# ERA_battery.net
KiCad netlist of a schematic drawn in EasyEDA
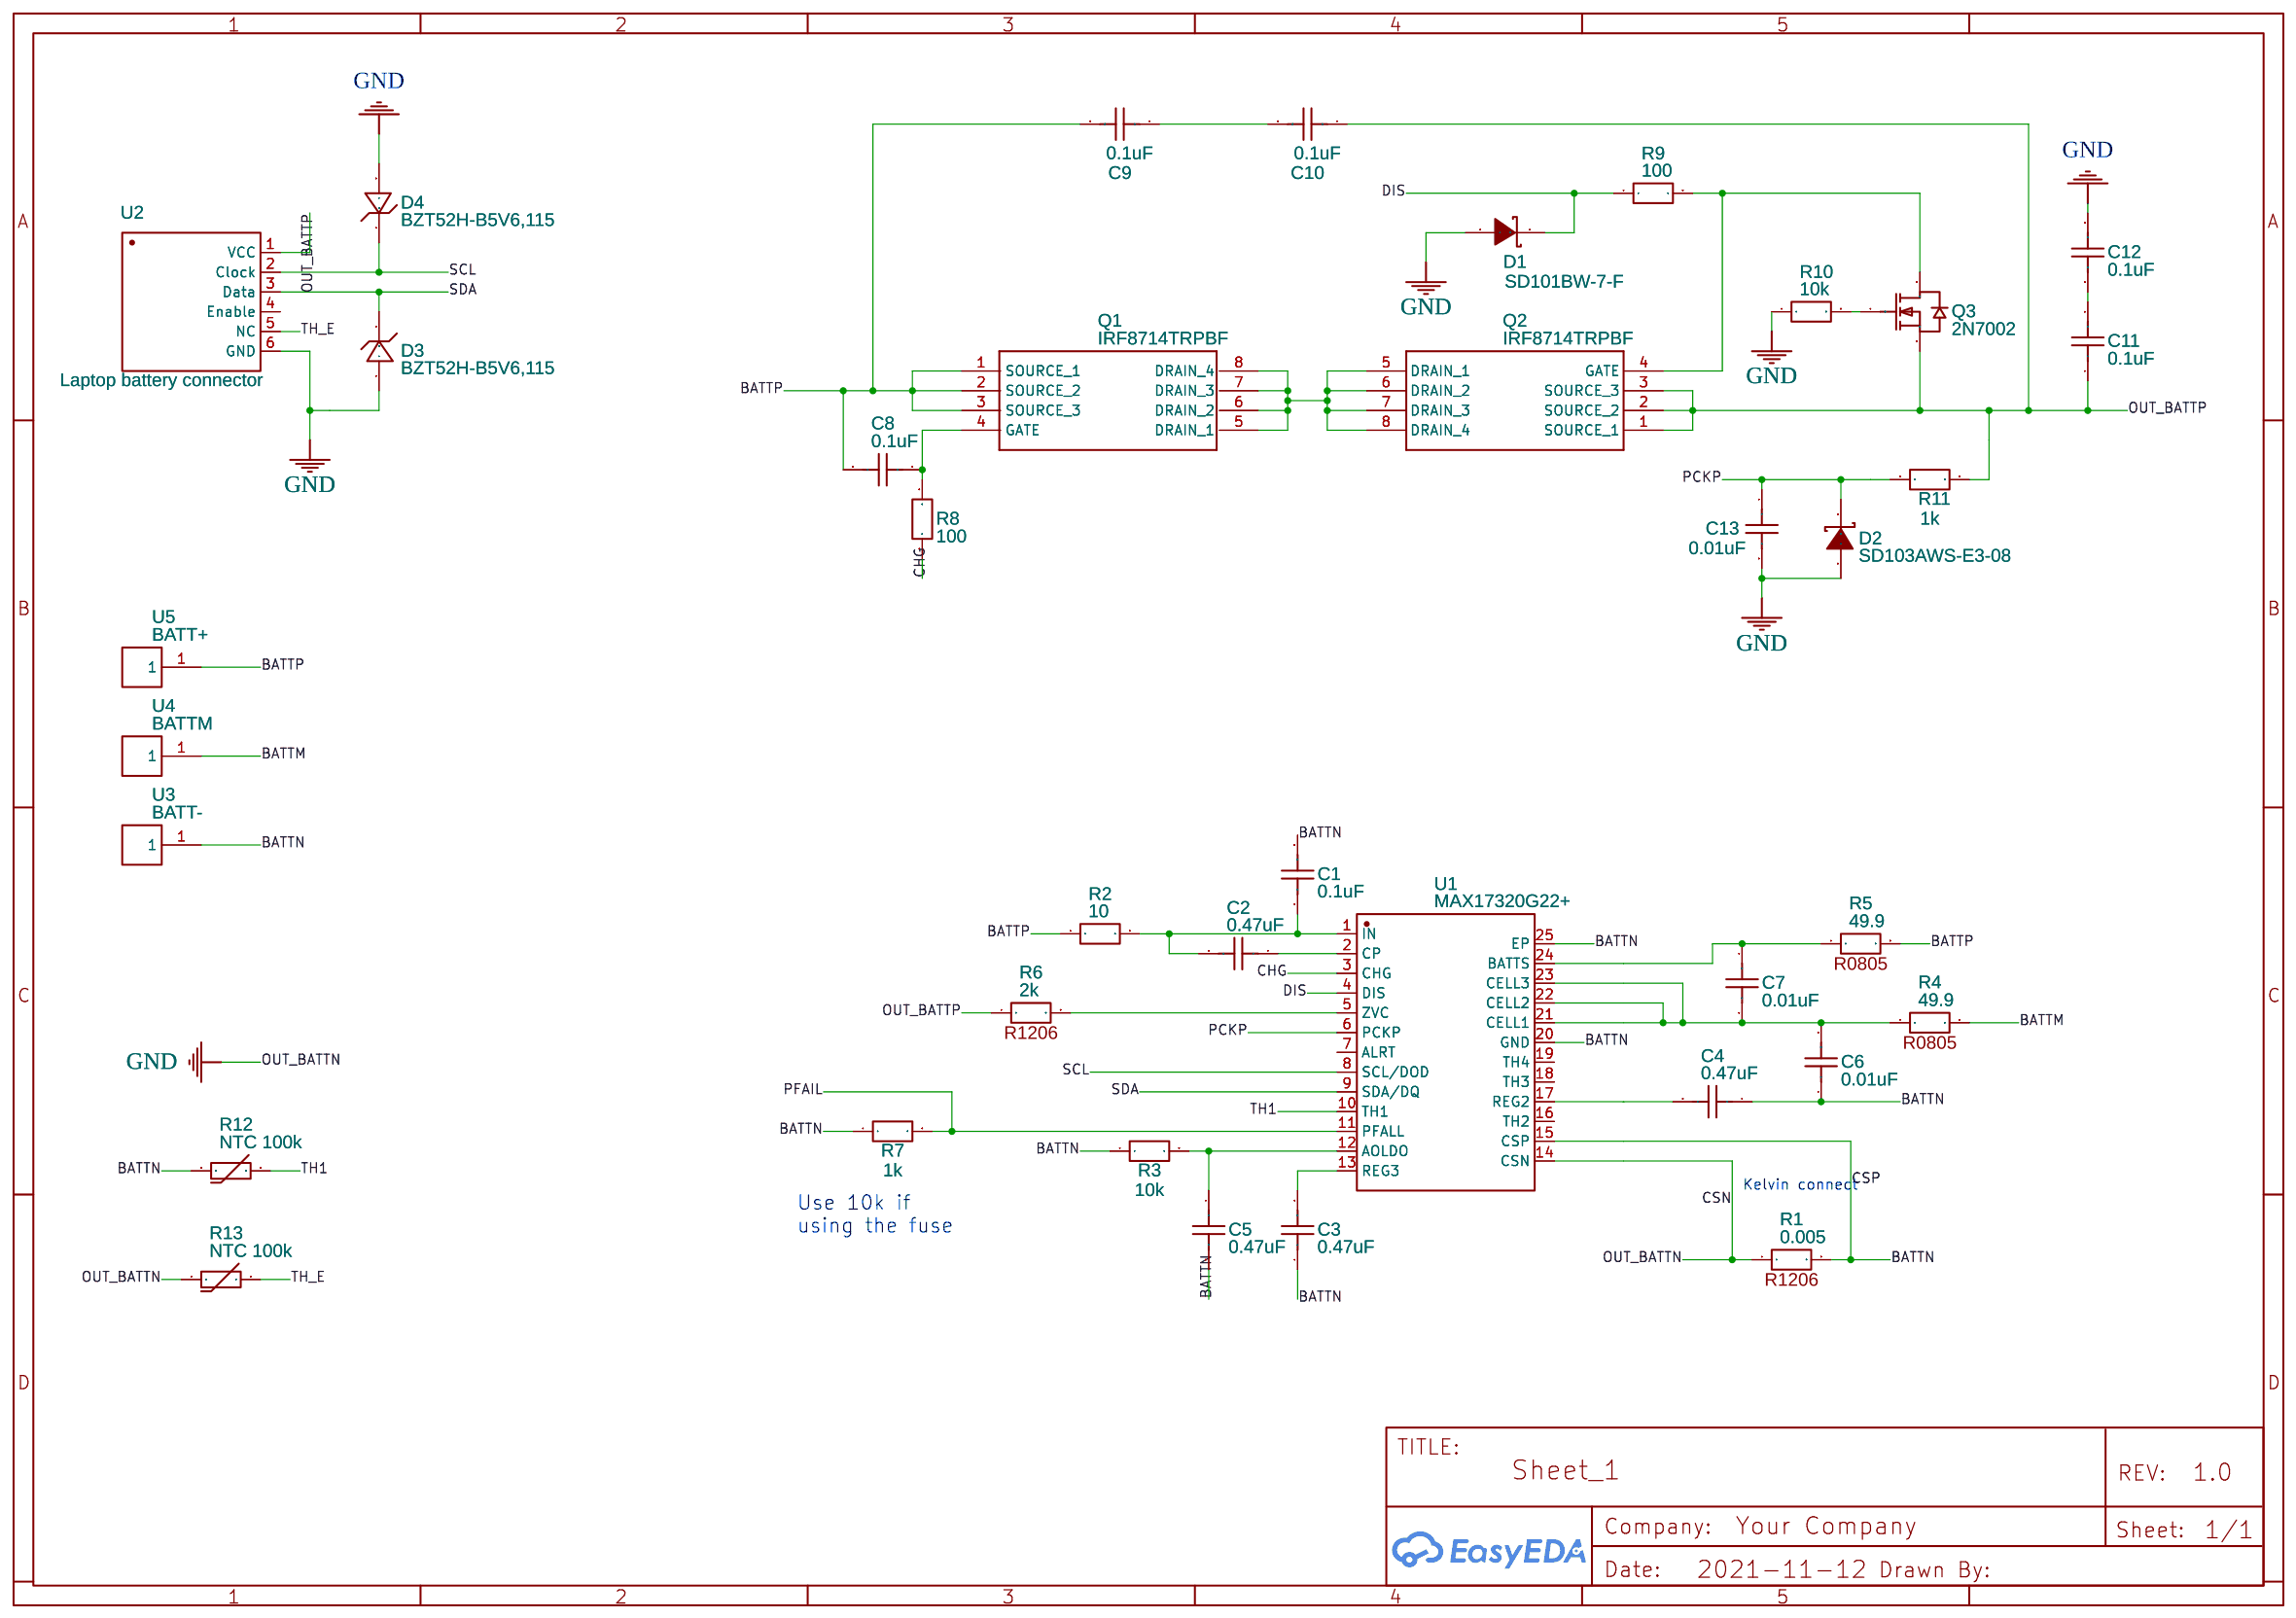
[diagram p0: schematic sheet]

(export (version "E")
  (design (tool "Eeschema 10.0.6"))
  (components
    (comp (ref "C1") (value "0.1uF") (libsource (lib "") (part "C_0603_US_1")))
    (comp (ref "C2") (value "0.47uF") (libsource (lib "") (part "C_0603_US")))
    (comp (ref "C3") (value "0.47uF") (libsource (lib "") (part "C_0603_US_1")))
    (comp (ref "C4") (value "0.47uF") (libsource (lib "") (part "C_0603_US")))
    (comp (ref "C5") (value "0.47uF") (libsource (lib "") (part "C_0603_US_2")))
    (comp (ref "C6") (value "0.01uF") (libsource (lib "") (part "C_0603_US_1")))
    (comp (ref "C7") (value "0.01uF") (libsource (lib "") (part "C_0603_US_2")))
    (comp (ref "C8") (value "0.1uF") (libsource (lib "") (part "C_0603_US")))
    (comp (ref "C9") (value "0.1uF") (libsource (lib "") (part "C_0603_US")))
    (comp (ref "C10") (value "0.1uF") (libsource (lib "") (part "C_0603_US")))
    (comp (ref "C11") (value "0.1uF") (libsource (lib "") (part "C_0603_US_1")))
    (comp (ref "C12") (value "0.1uF") (libsource (lib "") (part "C_0603_US_1")))
    (comp (ref "C13") (value "0.01uF") (libsource (lib "") (part "C_0603_US_2")))
    (comp (ref "D1")
      (value "SD101BW-7-F")
      (fields
        (field (name "BOM_Manufacturer Part") "SD101BWS-7-F")
        (field (name "BOM_Supplier Part") "C526757")
      )
      (libsource (lib "") (part "SD101BWS-7-F"))
    )
    (comp (ref "D2")
      (value "SD103AWS-E3-08")
      (fields (field (name "BOM_Supplier Part") "C142592"))
      (libsource (lib "") (part "SD103AWS-E3-08"))
    )
    (comp (ref "D3")
      (value "BZT52H-B5V6,115")
      (fields (field (name "BOM_Supplier Part") "C426804"))
      (libsource (lib "") (part "BZT52H-B5V6,115"))
    )
    (comp (ref "D4")
      (value "BZT52H-B5V6,115")
      (fields (field (name "BOM_Supplier Part") "C426804"))
      (libsource (lib "") (part "BZT52H-B5V6,115_1"))
    )
    (comp (ref "Q1") (value "IRF8714TRPBF") (libsource (lib "") (part "IRF8714TRPBF_1")))
    (comp (ref "Q2") (value "IRF8714TRPBF") (libsource (lib "") (part "IRF8714TRPBF")))
    (comp (ref "Q3")
      (value "2N7002")
      (fields (field (name "BOM_Supplier Part") "C8545"))
      (libsource (lib "") (part "2N7002"))
    )
    (comp (ref "R1") (value "0.005") (libsource (lib "") (part "R_1206_EU")))
    (comp (ref "R2") (value "10") (libsource (lib "") (part "R_0603_EU")))
    (comp (ref "R3") (value "10k") (libsource (lib "") (part "R_0603_EU")))
    (comp (ref "R4") (value "49.9") (libsource (lib "") (part "R_0805_EU")))
    (comp (ref "R5") (value "49.9") (libsource (lib "") (part "R_0805_EU")))
    (comp (ref "R6") (value "2k") (libsource (lib "") (part "R_1210_EU")))
    (comp (ref "R7") (value "1k") (libsource (lib "") (part "R_0603_EU")))
    (comp (ref "R8") (value "100") (libsource (lib "") (part "R_0603_EU_1")))
    (comp (ref "R9") (value "100") (libsource (lib "") (part "R_0603_EU")))
    (comp (ref "R10") (value "10k") (libsource (lib "") (part "R_0603_EU")))
    (comp (ref "R11") (value "1k") (libsource (lib "") (part "R_0603_EU")))
    (comp (ref "R12")
      (value "NTC 100k")
      (fields
        (field (name "BOM_Manufacturer Part") "CMFB102J3200HANT")
        (field (name "BOM_Supplier Part") "C75245")
      )
      (libsource (lib "") (part "CMFB102J3200HANT"))
    )
    (comp (ref "R13")
      (value "NTC 100k")
      (fields
        (field (name "BOM_Manufacturer Part") "CMFB102J3200HANT")
        (field (name "BOM_Supplier Part") "C75245")
      )
      (libsource (lib "") (part "CMFB102J3200HANT"))
    )
    (comp (ref "U1")
      (value "MAX17320G22+")
      (fields (field (name "BOM_Supplier Part") "C2914309"))
      (libsource (lib "") (part "MAX17320G22+"))
    )
    (comp (ref "U2")
      (value "Laptop battery connector")
      (libsource (lib "") (part "Laptop battery connector"))
    )
    (comp (ref "U3") (value "BATT-") (libsource (lib "") (part "PAD1")))
    (comp (ref "U4") (value "BATTM") (libsource (lib "") (part "PAD1")))
    (comp (ref "U5") (value "BATT+") (libsource (lib "") (part "PAD1")))
  )
  (nets
    (net (code "1") (name "/BATTM") (class "Default")
      (node (ref "R4") (pin "2") (pinfunction "2_2") (pintype "unspecified"))
      (node (ref "U4") (pin "1") (pinfunction "1_1") (pintype "unspecified"))
    )
    (net (code "2") (name "/BATTN") (class "Default")
      (node (ref "C1") (pin "2") (pinfunction "2_2") (pintype "unspecified"))
      (node (ref "C3") (pin "1") (pinfunction "1_1") (pintype "unspecified"))
      (node (ref "C4") (pin "1") (pinfunction "1_1") (pintype "unspecified"))
      (node (ref "C5") (pin "2") (pinfunction "2_2") (pintype "unspecified"))
      (node (ref "C6") (pin "1") (pinfunction "1_1") (pintype "unspecified"))
      (node (ref "R1") (pin "2") (pinfunction "2_2") (pintype "unspecified"))
      (node (ref "R12") (pin "1") (pinfunction "1_1") (pintype "input"))
      (node (ref "R3") (pin "1") (pinfunction "1_1") (pintype "unspecified"))
      (node (ref "R7") (pin "1") (pinfunction "1_1") (pintype "unspecified"))
      (node (ref "U1") (pin "15") (pinfunction "CSP_15") (pintype "unspecified"))
      (node (ref "U1") (pin "20") (pinfunction "GND_20") (pintype "unspecified"))
      (node (ref "U1") (pin "25") (pinfunction "EP_25") (pintype "unspecified"))
      (node (ref "U3") (pin "1") (pinfunction "1_1") (pintype "unspecified"))
    )
    (net (code "3") (name "/BATTP") (class "Default")
      (node (ref "C8") (pin "2") (pinfunction "2_2") (pintype "unspecified"))
      (node (ref "C9") (pin "2") (pinfunction "2_2") (pintype "unspecified"))
      (node (ref "Q1") (pin "1") (pinfunction "SOURCE_1_1") (pintype "bidirectional"))
      (node (ref "Q1") (pin "2") (pinfunction "SOURCE_2_2") (pintype "bidirectional"))
      (node (ref "Q1") (pin "3") (pinfunction "SOURCE_3_3") (pintype "bidirectional"))
      (node (ref "R2") (pin "1") (pinfunction "1_1") (pintype "unspecified"))
      (node (ref "R5") (pin "2") (pinfunction "2_2") (pintype "unspecified"))
      (node (ref "U5") (pin "1") (pinfunction "1_1") (pintype "unspecified"))
    )
    (net (code "4") (name "/CHG") (class "Default")
      (node (ref "R8") (pin "1") (pinfunction "1_1") (pintype "unspecified"))
      (node (ref "U1") (pin "3") (pinfunction "CHG_3") (pintype "unspecified"))
    )
    (net (code "5") (name "/DIS") (class "Default")
      (node (ref "D1") (pin "1") (pinfunction "C_1") (pintype "unspecified"))
      (node (ref "R9") (pin "1") (pinfunction "1_1") (pintype "unspecified"))
      (node (ref "U1") (pin "4") (pinfunction "DIS_4") (pintype "unspecified"))
    )
    (net (code "6") (name "/OUT_BATTP") (class "Default")
      (node (ref "C10") (pin "1") (pinfunction "1_1") (pintype "unspecified"))
      (node (ref "C11") (pin "1") (pinfunction "1_1") (pintype "unspecified"))
      (node (ref "Q2") (pin "1") (pinfunction "SOURCE_1_1") (pintype "bidirectional"))
      (node (ref "Q2") (pin "2") (pinfunction "SOURCE_2_2") (pintype "bidirectional"))
      (node (ref "Q2") (pin "3") (pinfunction "SOURCE_3_3") (pintype "bidirectional"))
      (node (ref "Q3") (pin "2") (pinfunction "S_2") (pintype "unspecified"))
      (node (ref "R11") (pin "2") (pinfunction "2_2") (pintype "unspecified"))
      (node (ref "R6") (pin "1") (pinfunction "1_1") (pintype "unspecified"))
      (node (ref "U2") (pin "1") (pinfunction "VCC_1") (pintype "unspecified"))
    )
    (net (code "7") (name "/PCKP") (class "Default")
      (node (ref "C13") (pin "1") (pinfunction "1_1") (pintype "unspecified"))
      (node (ref "D2") (pin "1") (pinfunction "K_1") (pintype "unspecified"))
      (node (ref "R11") (pin "1") (pinfunction "1_1") (pintype "unspecified"))
      (node (ref "U1") (pin "6") (pinfunction "PCKP_6") (pintype "unspecified"))
    )
    (net (code "8") (name "/PFAIL") (class "Default")
      (node (ref "R7") (pin "2") (pinfunction "2_2") (pintype "unspecified"))
      (node (ref "U1") (pin "11") (pinfunction "PFALL_11") (pintype "unspecified"))
    )
    (net (code "9") (name "/SCL") (class "Default")
      (node (ref "D4") (pin "1") (pinfunction "C_1") (pintype "unspecified"))
      (node (ref "U1") (pin "8") (pinfunction "SCL/DOD_8") (pintype "unspecified"))
      (node (ref "U2") (pin "2") (pinfunction "Clock_2") (pintype "unspecified"))
    )
    (net (code "10") (name "/SDA") (class "Default")
      (node (ref "D3") (pin "1") (pinfunction "C_1") (pintype "unspecified"))
      (node (ref "U1") (pin "9") (pinfunction "SDA/DQ_9") (pintype "unspecified"))
      (node (ref "U2") (pin "3") (pinfunction "Data_3") (pintype "unspecified"))
    )
    (net (code "11") (name "/TH1") (class "Default")
      (node (ref "R12") (pin "2") (pinfunction "2_2") (pintype "input"))
      (node (ref "U1") (pin "10") (pinfunction "TH1_10") (pintype "unspecified"))
    )
    (net (code "12") (name "/TH_E") (class "Default")
      (node (ref "R13") (pin "2") (pinfunction "2_2") (pintype "input"))
      (node (ref "U2") (pin "5") (pinfunction "NC_5") (pintype "unspecified"))
    )
    (net (code "13") (name "GND") (class "Default")
      (node (ref "C12") (pin "2") (pinfunction "2_2") (pintype "unspecified"))
      (node (ref "C13") (pin "2") (pinfunction "2_2") (pintype "unspecified"))
      (node (ref "D1") (pin "2") (pinfunction "A_2") (pintype "unspecified"))
      (node (ref "D2") (pin "2") (pinfunction "A_2") (pintype "unspecified"))
      (node (ref "D3") (pin "2") (pinfunction "A_2") (pintype "unspecified"))
      (node (ref "D4") (pin "2") (pinfunction "A_2") (pintype "unspecified"))
      (node (ref "R1") (pin "1") (pinfunction "1_1") (pintype "unspecified"))
      (node (ref "R10") (pin "1") (pinfunction "1_1") (pintype "unspecified"))
      (node (ref "R13") (pin "1") (pinfunction "1_1") (pintype "input"))
      (node (ref "U1") (pin "14") (pinfunction "CSN_14") (pintype "unspecified"))
      (node (ref "U2") (pin "6") (pinfunction "GND_6") (pintype "unspecified"))
    )
    (net (code "14") (name "Net-(C10-Pad2)") (class "Default")
      (node (ref "C10") (pin "2") (pinfunction "2_2") (pintype "unspecified"))
      (node (ref "C9") (pin "1") (pinfunction "1_1") (pintype "unspecified"))
    )
    (net (code "15") (name "Net-(C11-Pad2)") (class "Default")
      (node (ref "C11") (pin "2") (pinfunction "2_2") (pintype "unspecified"))
      (node (ref "C12") (pin "1") (pinfunction "1_1") (pintype "unspecified"))
    )
    (net (code "16") (name "Net-(Q1-DRAIN_1)") (class "Default")
      (node (ref "Q1") (pin "5") (pinfunction "DRAIN_1_5") (pintype "bidirectional"))
      (node (ref "Q1") (pin "6") (pinfunction "DRAIN_2_6") (pintype "bidirectional"))
      (node (ref "Q1") (pin "7") (pinfunction "DRAIN_3_7") (pintype "bidirectional"))
      (node (ref "Q1") (pin "8") (pinfunction "DRAIN_4_8") (pintype "bidirectional"))
      (node (ref "Q2") (pin "5") (pinfunction "DRAIN_1_5") (pintype "bidirectional"))
      (node (ref "Q2") (pin "6") (pinfunction "DRAIN_2_6") (pintype "bidirectional"))
      (node (ref "Q2") (pin "7") (pinfunction "DRAIN_3_7") (pintype "bidirectional"))
      (node (ref "Q2") (pin "8") (pinfunction "DRAIN_4_8") (pintype "bidirectional"))
    )
    (net (code "17") (name "Net-(Q1-GATE)") (class "Default")
      (node (ref "C8") (pin "1") (pinfunction "1_1") (pintype "unspecified"))
      (node (ref "Q1") (pin "4") (pinfunction "GATE_4") (pintype "bidirectional"))
      (node (ref "R8") (pin "2") (pinfunction "2_2") (pintype "unspecified"))
    )
    (net (code "18") (name "Net-(Q2-GATE)") (class "Default")
      (node (ref "Q2") (pin "4") (pinfunction "GATE_4") (pintype "bidirectional"))
      (node (ref "Q3") (pin "3") (pinfunction "D_3") (pintype "unspecified"))
      (node (ref "R9") (pin "2") (pinfunction "2_2") (pintype "unspecified"))
    )
    (net (code "19") (name "Net-(Q3-G)") (class "Default")
      (node (ref "Q3") (pin "1") (pinfunction "G_1") (pintype "unspecified"))
      (node (ref "R10") (pin "2") (pinfunction "2_2") (pintype "unspecified"))
    )
    (net (code "20") (name "Net-(U1-AOLDO)") (class "Default")
      (node (ref "C5") (pin "1") (pinfunction "1_1") (pintype "unspecified"))
      (node (ref "R3") (pin "2") (pinfunction "2_2") (pintype "unspecified"))
      (node (ref "U1") (pin "12") (pinfunction "AOLDO_12") (pintype "unspecified"))
    )
    (net (code "21") (name "Net-(U1-BATTS)") (class "Default")
      (node (ref "C7") (pin "1") (pinfunction "1_1") (pintype "unspecified"))
      (node (ref "R5") (pin "1") (pinfunction "1_1") (pintype "unspecified"))
      (node (ref "U1") (pin "24") (pinfunction "BATTS_24") (pintype "unspecified"))
    )
    (net (code "22") (name "Net-(U1-CELL1)") (class "Default")
      (node (ref "C6") (pin "2") (pinfunction "2_2") (pintype "unspecified"))
      (node (ref "C7") (pin "2") (pinfunction "2_2") (pintype "unspecified"))
      (node (ref "R4") (pin "1") (pinfunction "1_1") (pintype "unspecified"))
      (node (ref "U1") (pin "21") (pinfunction "CELL1_21") (pintype "unspecified"))
      (node (ref "U1") (pin "22") (pinfunction "CELL2_22") (pintype "unspecified"))
      (node (ref "U1") (pin "23") (pinfunction "CELL3_23") (pintype "unspecified"))
    )
    (net (code "23") (name "Net-(U1-CP)") (class "Default")
      (node (ref "C2") (pin "1") (pinfunction "1_1") (pintype "unspecified"))
      (node (ref "U1") (pin "2") (pinfunction "CP_2") (pintype "unspecified"))
    )
    (net (code "24") (name "Net-(U1-IN)") (class "Default")
      (node (ref "C1") (pin "1") (pinfunction "1_1") (pintype "unspecified"))
      (node (ref "C2") (pin "2") (pinfunction "2_2") (pintype "unspecified"))
      (node (ref "R2") (pin "2") (pinfunction "2_2") (pintype "unspecified"))
      (node (ref "U1") (pin "1") (pinfunction "IN_1") (pintype "unspecified"))
    )
    (net (code "25") (name "Net-(U1-REG2)") (class "Default")
      (node (ref "C4") (pin "2") (pinfunction "2_2") (pintype "unspecified"))
      (node (ref "U1") (pin "17") (pinfunction "REG2_17") (pintype "unspecified"))
    )
    (net (code "26") (name "Net-(U1-REG3)") (class "Default")
      (node (ref "C3") (pin "2") (pinfunction "2_2") (pintype "unspecified"))
      (node (ref "U1") (pin "13") (pinfunction "REG3_13") (pintype "unspecified"))
    )
    (net (code "27") (name "Net-(U1-ZVC)") (class "Default")
      (node (ref "R6") (pin "2") (pinfunction "2_2") (pintype "unspecified"))
      (node (ref "U1") (pin "5") (pinfunction "ZVC_5") (pintype "unspecified"))
    )
    (net (code "28") (name "unconnected-(U1-ALRT-Pad7)") (class "Default")
      (node (ref "U1") (pin "7") (pinfunction "ALRT_7") (pintype "unspecified"))
    )
    (net (code "29") (name "unconnected-(U1-TH2-Pad16)") (class "Default")
      (node (ref "U1") (pin "16") (pinfunction "TH2_16") (pintype "unspecified"))
    )
    (net (code "30") (name "unconnected-(U1-TH3-Pad18)") (class "Default")
      (node (ref "U1") (pin "18") (pinfunction "TH3_18") (pintype "unspecified"))
    )
    (net (code "31") (name "unconnected-(U1-TH4-Pad19)") (class "Default")
      (node (ref "U1") (pin "19") (pinfunction "TH4_19") (pintype "unspecified"))
    )
    (net (code "32") (name "unconnected-(U2-Enable-Pad4)") (class "Default")
      (node (ref "U2") (pin "4") (pinfunction "Enable_4") (pintype "unspecified"))
    )
  )
)
